# ums.net
KiCad netlist of a schematic drawn in EAGLE
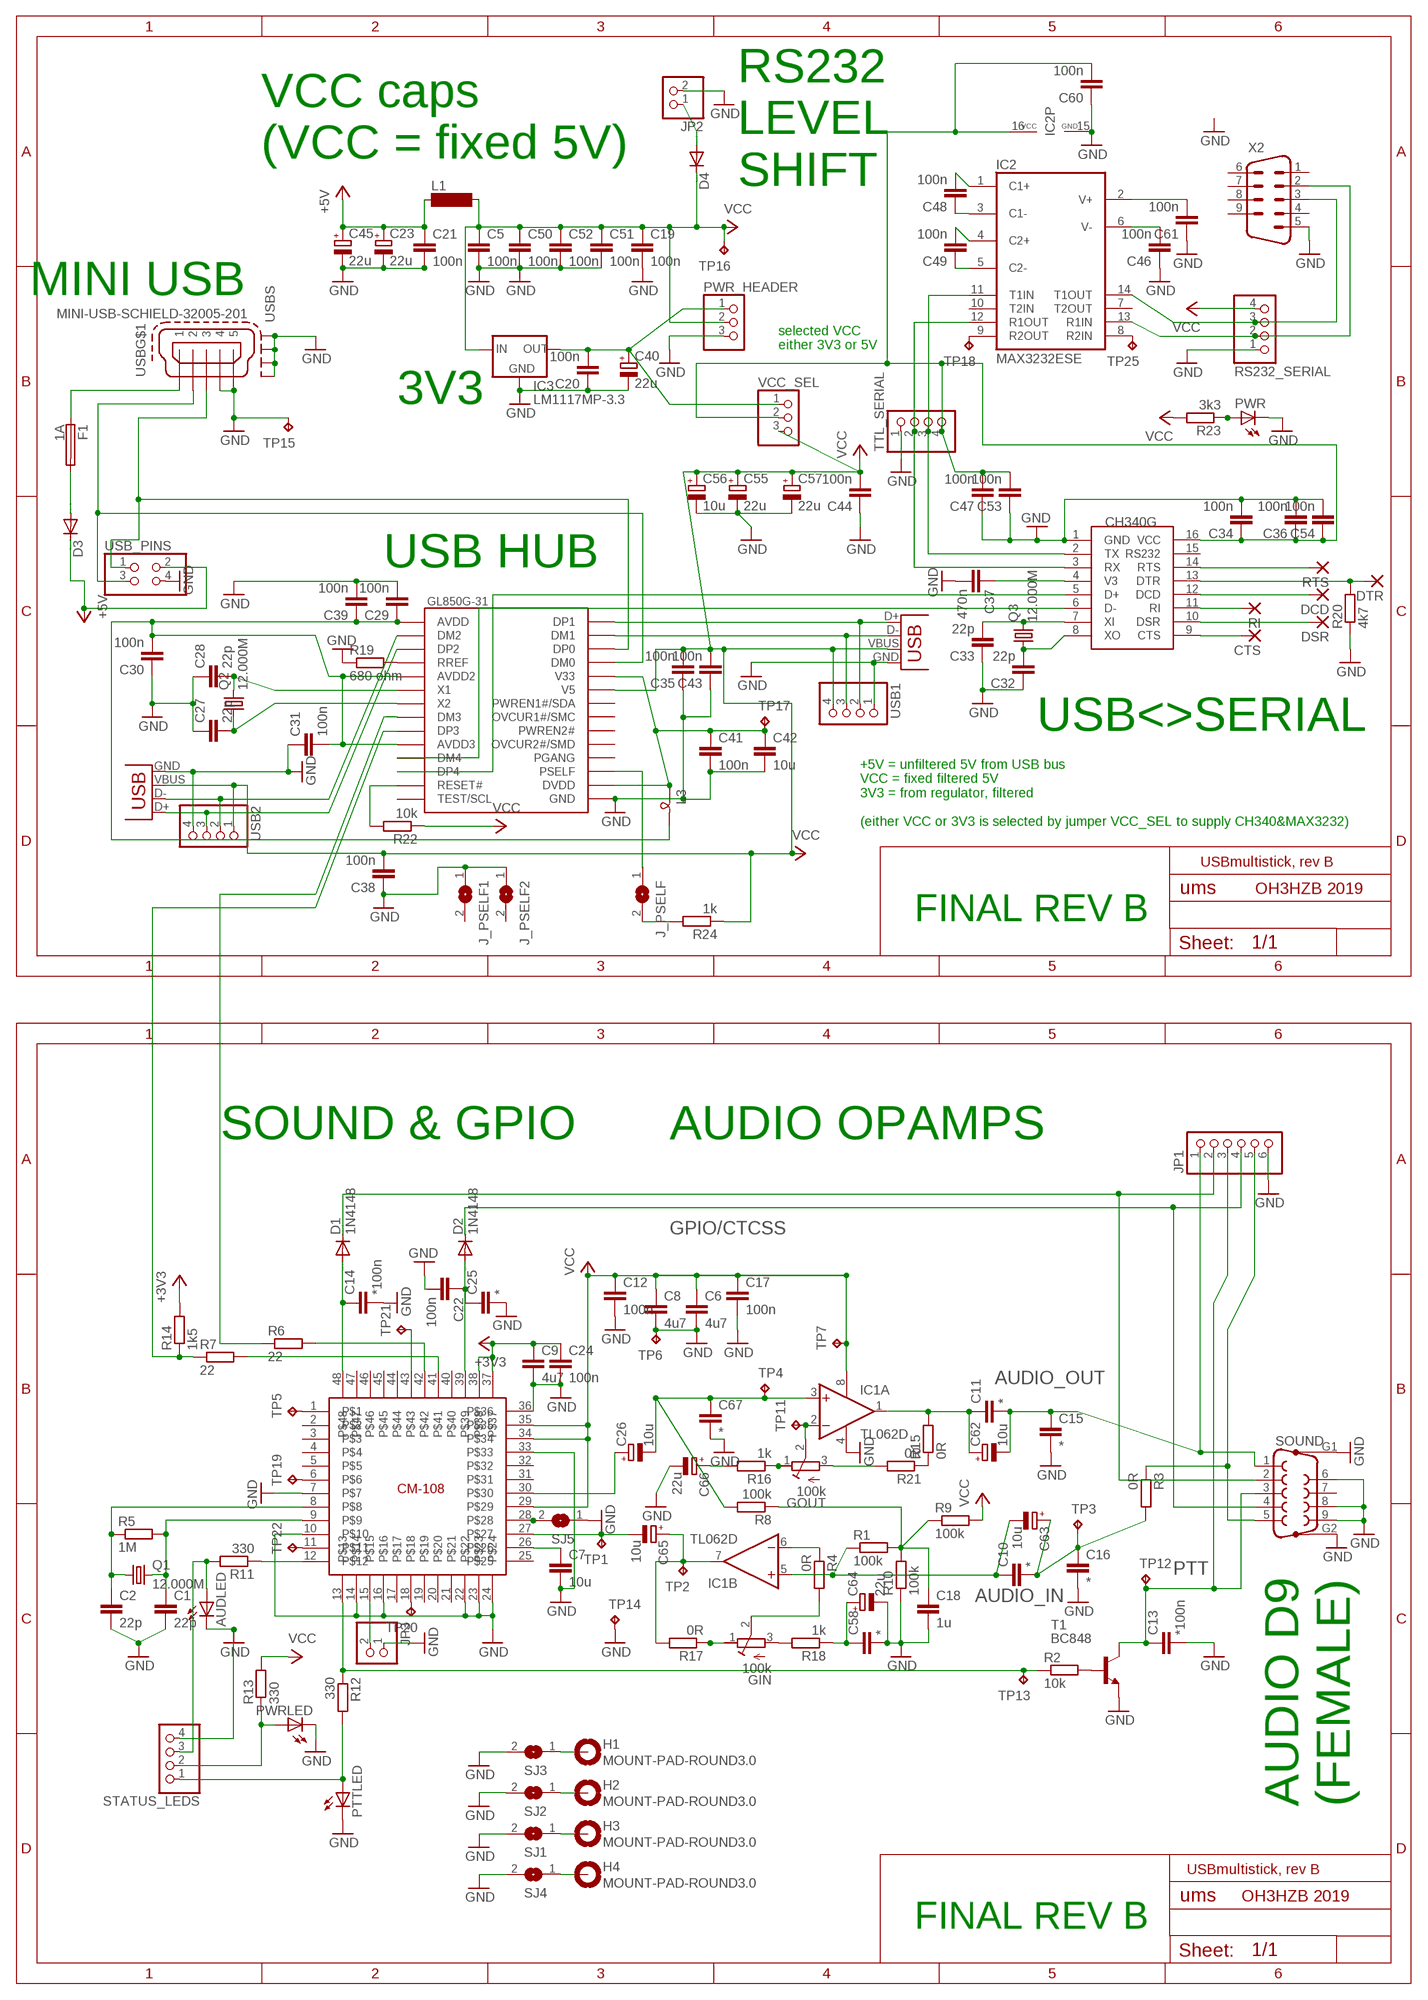
[diagram p0: schematic, sheet 1]

(export (version "E")
  (design (tool "Eeschema 10.0.6"))
  (components
    (comp (ref "AUDLED")
      (value "LED3MM")
      (footprint "eagle-import:LED3MM")
      (libsource (lib "eagle-import") (part "LED3MM"))
    )
    (comp (ref "C1")
      (value "22p")
      (footprint "eagle-import:C1206K")
      (libsource (lib "eagle-import") (part "C-EUC1206K"))
    )
    (comp (ref "C2")
      (value "22p")
      (footprint "eagle-import:C1206K")
      (libsource (lib "eagle-import") (part "C-EUC1206K"))
    )
    (comp (ref "C5")
      (value "100n")
      (footprint "eagle-import:C1206K")
      (libsource (lib "eagle-import") (part "C-EUC1206K"))
    )
    (comp (ref "C6")
      (value "4u7")
      (footprint "eagle-import:C1206K")
      (libsource (lib "eagle-import") (part "C-EUC1206K"))
    )
    (comp (ref "C7")
      (value "10u")
      (footprint "eagle-import:C1206K")
      (libsource (lib "eagle-import") (part "C-EUC1206K"))
    )
    (comp (ref "C8")
      (value "4u7")
      (footprint "eagle-import:C1206K")
      (libsource (lib "eagle-import") (part "C-EUC1206K"))
    )
    (comp (ref "C9")
      (value "4u7")
      (footprint "eagle-import:C1206K")
      (libsource (lib "eagle-import") (part "C-EUC1206K"))
    )
    (comp (ref "C10")
      (value "*")
      (footprint "eagle-import:C1206K")
      (libsource (lib "eagle-import") (part "C-EUC1206K"))
    )
    (comp (ref "C11")
      (value "*")
      (footprint "eagle-import:C1206K")
      (libsource (lib "eagle-import") (part "C-EUC1206K"))
    )
    (comp (ref "C12")
      (value "100n")
      (footprint "eagle-import:C1206K")
      (libsource (lib "eagle-import") (part "C-EUC1206K"))
    )
    (comp (ref "C13")
      (value "*100n")
      (footprint "eagle-import:C1206K")
      (libsource (lib "eagle-import") (part "C-EUC1206K"))
    )
    (comp (ref "C14")
      (value "*100n")
      (footprint "eagle-import:C1206K")
      (libsource (lib "eagle-import") (part "C-EUC1206K"))
    )
    (comp (ref "C15")
      (value "*")
      (footprint "eagle-import:C0805")
      (libsource (lib "eagle-import") (part "C-EUC0805"))
    )
    (comp (ref "C16")
      (value "*")
      (footprint "eagle-import:C1206K")
      (libsource (lib "eagle-import") (part "C-EUC1206K"))
    )
    (comp (ref "C17")
      (value "100n")
      (footprint "eagle-import:C0805")
      (libsource (lib "eagle-import") (part "C-EUC0805"))
    )
    (comp (ref "C18")
      (value "1u")
      (footprint "eagle-import:C4532")
      (libsource (lib "eagle-import") (part "C-EUC4532"))
    )
    (comp (ref "C19")
      (value "100n")
      (footprint "eagle-import:C0805")
      (libsource (lib "eagle-import") (part "C-EUC0805"))
    )
    (comp (ref "C20")
      (value "100n")
      (footprint "eagle-import:C0805")
      (libsource (lib "eagle-import") (part "C-EUC0805"))
    )
    (comp (ref "C21")
      (value "100n")
      (footprint "eagle-import:C0805")
      (libsource (lib "eagle-import") (part "C-EUC0805"))
    )
    (comp (ref "C22")
      (value "100n")
      (footprint "eagle-import:C0805")
      (libsource (lib "eagle-import") (part "C-EUC0805"))
    )
    (comp (ref "C23")
      (value "22u")
      (footprint "eagle-import:D_7343-31W")
      (libsource (lib "eagle-import") (part "CPOL-EUD/7343-31W"))
    )
    (comp (ref "C24")
      (value "100n")
      (footprint "eagle-import:C0805")
      (libsource (lib "eagle-import") (part "C-EUC0805"))
    )
    (comp (ref "C25")
      (value "*")
      (footprint "eagle-import:C0805")
      (libsource (lib "eagle-import") (part "C-EUC0805"))
    )
    (comp (ref "C26")
      (value "10u")
      (footprint "eagle-import:153CLV-0605")
      (libsource (lib "eagle-import") (part "CPOL-EU153CLV-0605"))
    )
    (comp (ref "C27")
      (value "22p")
      (footprint "eagle-import:C1206K")
      (libsource (lib "eagle-import") (part "C-EUC1206K"))
    )
    (comp (ref "C28")
      (value "22p")
      (footprint "eagle-import:C1206K")
      (libsource (lib "eagle-import") (part "C-EUC1206K"))
    )
    (comp (ref "C29")
      (value "100n")
      (footprint "eagle-import:C0805")
      (libsource (lib "eagle-import") (part "C-EUC0805"))
    )
    (comp (ref "C30")
      (value "100n")
      (footprint "eagle-import:C0805")
      (libsource (lib "eagle-import") (part "C-EUC0805"))
    )
    (comp (ref "C31")
      (value "100n")
      (footprint "eagle-import:C1206")
      (libsource (lib "eagle-import") (part "C-EUC1206"))
    )
    (comp (ref "C32")
      (value "22p")
      (footprint "eagle-import:C1206K")
      (libsource (lib "eagle-import") (part "C-EUC1206K"))
    )
    (comp (ref "C33")
      (value "22p")
      (footprint "eagle-import:C1206K")
      (libsource (lib "eagle-import") (part "C-EUC1206K"))
    )
    (comp (ref "C34")
      (value "100n")
      (footprint "eagle-import:C0805")
      (libsource (lib "eagle-import") (part "C-EUC0805"))
    )
    (comp (ref "C35")
      (value "100n")
      (footprint "eagle-import:C0805")
      (libsource (lib "eagle-import") (part "C-EUC0805"))
    )
    (comp (ref "C36")
      (value "100n")
      (footprint "eagle-import:C0805")
      (libsource (lib "eagle-import") (part "C-EUC0805"))
    )
    (comp (ref "C37")
      (value "470n")
      (footprint "eagle-import:C0805")
      (libsource (lib "eagle-import") (part "C-EUC0805"))
    )
    (comp (ref "C38")
      (value "100n")
      (footprint "eagle-import:C0805")
      (libsource (lib "eagle-import") (part "C-EUC0805"))
    )
    (comp (ref "C39")
      (value "100n")
      (footprint "eagle-import:C0805")
      (libsource (lib "eagle-import") (part "C-EUC0805"))
    )
    (comp (ref "C40")
      (value "22u")
      (footprint "eagle-import:SMC_B")
      (libsource (lib "eagle-import") (part "CPOL-EUSMCB"))
    )
    (comp (ref "C41")
      (value "100n")
      (footprint "eagle-import:C0805")
      (libsource (lib "eagle-import") (part "C-EUC0805"))
    )
    (comp (ref "C42")
      (value "10u")
      (footprint "eagle-import:C0805")
      (libsource (lib "eagle-import") (part "C-EUC0805"))
    )
    (comp (ref "C43")
      (value "100n")
      (footprint "eagle-import:C0805")
      (libsource (lib "eagle-import") (part "C-EUC0805"))
    )
    (comp (ref "C44")
      (value "100n")
      (footprint "eagle-import:C0805")
      (libsource (lib "eagle-import") (part "C-EUC0805"))
    )
    (comp (ref "C45")
      (value "22u")
      (footprint "eagle-import:D_7343-31W")
      (libsource (lib "eagle-import") (part "CPOL-EUD/7343-31W"))
    )
    (comp (ref "C46")
      (value "100n")
      (footprint "eagle-import:C0805")
      (libsource (lib "eagle-import") (part "C-EUC0805"))
    )
    (comp (ref "C47")
      (value "100n")
      (footprint "eagle-import:C0805")
      (libsource (lib "eagle-import") (part "C-EUC0805"))
    )
    (comp (ref "C48")
      (value "100n")
      (footprint "eagle-import:C0805")
      (libsource (lib "eagle-import") (part "C-EUC0805"))
    )
    (comp (ref "C49")
      (value "100n")
      (footprint "eagle-import:C0805")
      (libsource (lib "eagle-import") (part "C-EUC0805"))
    )
    (comp (ref "C50")
      (value "100n")
      (footprint "eagle-import:C0805")
      (libsource (lib "eagle-import") (part "C-EUC0805"))
    )
    (comp (ref "C51")
      (value "100n")
      (footprint "eagle-import:C0805")
      (libsource (lib "eagle-import") (part "C-EUC0805"))
    )
    (comp (ref "C52")
      (value "100n")
      (footprint "eagle-import:C0805")
      (libsource (lib "eagle-import") (part "C-EUC0805"))
    )
    (comp (ref "C53")
      (value "100n")
      (footprint "eagle-import:C0805")
      (libsource (lib "eagle-import") (part "C-EUC0805"))
    )
    (comp (ref "C54")
      (value "100n")
      (footprint "eagle-import:C1206")
      (libsource (lib "eagle-import") (part "C-EUC1206"))
    )
    (comp (ref "C55")
      (value "22u")
      (footprint "eagle-import:C_6032-28R")
      (libsource (lib "eagle-import") (part "CPOL-EUC/6032-28R"))
    )
    (comp (ref "C56")
      (value "10u")
      (footprint "eagle-import:SMC_B")
      (libsource (lib "eagle-import") (part "CPOL-EUSMCB"))
    )
    (comp (ref "C57")
      (value "22u")
      (footprint "eagle-import:CT6032")
      (libsource (lib "eagle-import") (part "CPOL-EUCT6032"))
    )
    (comp (ref "C58")
      (value "*")
      (footprint "eagle-import:C1206K")
      (libsource (lib "eagle-import") (part "C-EUC1206K"))
    )
    (comp (ref "C60")
      (value "100n")
      (footprint "eagle-import:C0805")
      (libsource (lib "eagle-import") (part "C-EUC0805"))
    )
    (comp (ref "C61")
      (value "100n")
      (footprint "eagle-import:C0805")
      (libsource (lib "eagle-import") (part "C-EUC0805"))
    )
    (comp (ref "C62")
      (value "10u")
      (footprint "eagle-import:153CLV-0605")
      (libsource (lib "eagle-import") (part "CPOL-EU153CLV-0605"))
    )
    (comp (ref "C63")
      (value "10u")
      (footprint "eagle-import:153CLV-0605")
      (libsource (lib "eagle-import") (part "CPOL-EU153CLV-0605"))
    )
    (comp (ref "C64")
      (value "22u")
      (footprint "eagle-import:153CLV-0605")
      (libsource (lib "eagle-import") (part "CPOL-EU153CLV-0605"))
    )
    (comp (ref "C65")
      (value "10u")
      (footprint "eagle-import:153CLV-0605")
      (libsource (lib "eagle-import") (part "CPOL-EU153CLV-0605"))
    )
    (comp (ref "C66")
      (value "22u")
      (footprint "eagle-import:153CLV-0605")
      (libsource (lib "eagle-import") (part "CPOL-EU153CLV-0605"))
    )
    (comp (ref "C67")
      (value "*")
      (footprint "eagle-import:C0805")
      (libsource (lib "eagle-import") (part "C-EUC0805"))
    )
    (comp (ref "CTS")
      (value "SMD2")
      (footprint "eagle-import:SMD1,27-2,54")
      (libsource (lib "eagle-import") (part "SMD2"))
    )
    (comp (ref "D1")
      (value "1N4148")
      (footprint "eagle-import:SOD123")
      (libsource (lib "eagle-import") (part "DIODE-SOD123"))
    )
    (comp (ref "D2")
      (value "1N4148")
      (footprint "eagle-import:SOD323-W")
      (libsource (lib "eagle-import") (part "DIODE-SOD323-W"))
    )
    (comp (ref "D3")
      (value "DIODE-DO214AC")
      (footprint "eagle-import:DO214AC")
      (libsource (lib "eagle-import") (part "DIODE-DO214AC"))
    )
    (comp (ref "D4")
      (value "DIODE-DO214AC")
      (footprint "eagle-import:DO214AC")
      (libsource (lib "eagle-import") (part "DIODE-DO214AC"))
    )
    (comp (ref "DCD")
      (value "SMD2")
      (footprint "eagle-import:SMD1,27-2,54")
      (libsource (lib "eagle-import") (part "SMD2"))
    )
    (comp (ref "DSR")
      (value "SMD2")
      (footprint "eagle-import:SMD1,27-2,54")
      (libsource (lib "eagle-import") (part "SMD2"))
    )
    (comp (ref "DTR")
      (value "SMD2")
      (footprint "eagle-import:SMD1,27-2,54")
      (libsource (lib "eagle-import") (part "SMD2"))
    )
    (comp (ref "F1")
      (value "1A")
      (footprint "eagle-import:TE5")
      (libsource (lib "eagle-import") (part "TE5"))
    )
    (comp (ref "GIN")
      (value "100k")
      (footprint "eagle-import:RTRIMT93YA")
      (libsource (lib "eagle-import") (part "R-TRIMMT93YA"))
    )
    (comp (ref "GOUT")
      (value "100k")
      (footprint "eagle-import:RTRIMT93YA")
      (libsource (lib "eagle-import") (part "R-TRIMMT93YA"))
    )
    (comp (ref "H1")
      (value "MOUNT-PAD-ROUND3.0")
      (footprint "eagle-import:3,0-PAD")
      (libsource (lib "eagle-import") (part "MOUNT-PAD-ROUND3.0"))
    )
    (comp (ref "H2")
      (value "MOUNT-PAD-ROUND3.0")
      (footprint "eagle-import:3,0-PAD")
      (libsource (lib "eagle-import") (part "MOUNT-PAD-ROUND3.0"))
    )
    (comp (ref "H3")
      (value "MOUNT-PAD-ROUND3.0")
      (footprint "eagle-import:3,0-PAD")
      (libsource (lib "eagle-import") (part "MOUNT-PAD-ROUND3.0"))
    )
    (comp (ref "H4")
      (value "MOUNT-PAD-ROUND3.0")
      (footprint "eagle-import:3,0-PAD")
      (libsource (lib "eagle-import") (part "MOUNT-PAD-ROUND3.0"))
    )
    (comp (ref "IC1")
      (value "TL062D")
      (footprint "eagle-import:SO08")
      (libsource (lib "eagle-import") (part "TL062D"))
    )
    (comp (ref "IC2")
      (value "MAX3232ESE")
      (footprint "eagle-import:SO16")
      (fields (field (name "MF") "MAXIM"))
      (libsource (lib "eagle-import") (part "MAX3232SEE"))
    )
    (comp (ref "IC3")
      (value "LM1117MP-3.3")
      (footprint "eagle-import:SOT223")
      (fields (field (name "MF") "Texas Instruments"))
      (libsource (lib "eagle-import") (part "LM1117?-MP3.3"))
    )
    (comp (ref "IC4")
      (value "GL850G-31")
      (footprint "eagle-import:TSSOP28")
      (libsource (lib "eagle-import") (part "GL850G-31"))
    )
    (comp (ref "JP1")
      (value "PINHD-1X6")
      (footprint "eagle-import:1X06")
      (libsource (lib "eagle-import") (part "PINHD-1X6"))
    )
    (comp (ref "JP2")
      (value "PINHD-1X2")
      (footprint "eagle-import:1X02")
      (libsource (lib "eagle-import") (part "PINHD-1X2"))
    )
    (comp (ref "JP3")
      (value "PINHD-1X2")
      (footprint "eagle-import:1X02")
      (libsource (lib "eagle-import") (part "PINHD-1X2"))
    )
    (comp (ref "J_PSELF")
      (value "SJ")
      (footprint "eagle-import:SJ")
      (libsource (lib "eagle-import") (part "SJ"))
    )
    (comp (ref "J_PSELF1")
      (value "SJ")
      (footprint "eagle-import:SJ")
      (libsource (lib "eagle-import") (part "SJ"))
    )
    (comp (ref "J_PSELF2")
      (value "SJ")
      (footprint "eagle-import:SJ")
      (libsource (lib "eagle-import") (part "SJ"))
    )
    (comp (ref "L1")
      (value "SM-1206")
      (footprint "eagle-import:SM-1206")
      (libsource (lib "eagle-import") (part "SM-1206"))
    )
    (comp (ref "L3")
      (value "SM-B5")
      (footprint "eagle-import:SM-B5")
      (libsource (lib "eagle-import") (part "SM-B5"))
    )
    (comp (ref "PTTLED")
      (value "LED3MM")
      (footprint "eagle-import:LED3MM")
      (libsource (lib "eagle-import") (part "LED3MM"))
    )
    (comp (ref "PWR")
      (value "LEDCHIPLED_0805")
      (footprint "eagle-import:CHIPLED_0805")
      (libsource (lib "eagle-import") (part "LEDCHIPLED_0805"))
    )
    (comp (ref "PWRLED")
      (value "LED3MM")
      (footprint "eagle-import:LED3MM")
      (libsource (lib "eagle-import") (part "LED3MM"))
    )
    (comp (ref "PWR_HEADER")
      (value "PINHD-1X3")
      (footprint "eagle-import:1X03")
      (libsource (lib "eagle-import") (part "PINHD-1X3"))
    )
    (comp (ref "Q1")
      (value "12.000M")
      (footprint "eagle-import:SM49")
      (libsource (lib "eagle-import") (part "CRYSTALSM49"))
    )
    (comp (ref "Q2")
      (value "12.000M")
      (footprint "eagle-import:SM49")
      (libsource (lib "eagle-import") (part "CRYSTALSM49"))
    )
    (comp (ref "Q3")
      (value "12.000M")
      (footprint "eagle-import:SM49")
      (libsource (lib "eagle-import") (part "CRYSTALSM49"))
    )
    (comp (ref "R1")
      (value "100k")
      (footprint "eagle-import:R1206")
      (libsource (lib "eagle-import") (part "resistor_R-EU_R1206"))
    )
    (comp (ref "R2")
      (value "10k")
      (footprint "eagle-import:R1206")
      (libsource (lib "eagle-import") (part "resistor_R-EU_R1206"))
    )
    (comp (ref "R3")
      (value "0R")
      (footprint "eagle-import:R1206")
      (libsource (lib "eagle-import") (part "resistor_R-EU_R1206"))
    )
    (comp (ref "R4")
      (value "0R")
      (footprint "eagle-import:R1206")
      (libsource (lib "eagle-import") (part "resistor_R-EU_R1206"))
    )
    (comp (ref "R5")
      (value "1M")
      (footprint "eagle-import:R1206")
      (libsource (lib "eagle-import") (part "resistor_R-EU_R1206"))
    )
    (comp (ref "R6")
      (value "22")
      (footprint "eagle-import:R1206")
      (libsource (lib "eagle-import") (part "resistor_R-EU_R1206"))
    )
    (comp (ref "R7")
      (value "22")
      (footprint "eagle-import:R1206")
      (libsource (lib "eagle-import") (part "resistor_R-EU_R1206"))
    )
    (comp (ref "R8")
      (value "100k")
      (footprint "eagle-import:R1206")
      (libsource (lib "eagle-import") (part "resistor_R-EU_R1206"))
    )
    (comp (ref "R9")
      (value "100k")
      (footprint "eagle-import:R1206")
      (libsource (lib "eagle-import") (part "resistor_R-EU_R1206"))
    )
    (comp (ref "R10")
      (value "100k")
      (footprint "eagle-import:R1206")
      (libsource (lib "eagle-import") (part "resistor_R-EU_R1206"))
    )
    (comp (ref "R11")
      (value "330")
      (footprint "eagle-import:R1206")
      (libsource (lib "eagle-import") (part "resistor_R-EU_R1206"))
    )
    (comp (ref "R12")
      (value "330")
      (footprint "eagle-import:R1206")
      (libsource (lib "eagle-import") (part "resistor_R-EU_R1206"))
    )
    (comp (ref "R13")
      (value "330")
      (footprint "eagle-import:R1206")
      (libsource (lib "eagle-import") (part "resistor_R-EU_R1206"))
    )
    (comp (ref "R14")
      (value "1k5")
      (footprint "eagle-import:R1206")
      (libsource (lib "eagle-import") (part "resistor_R-EU_R1206"))
    )
    (comp (ref "R15")
      (value "0R")
      (footprint "eagle-import:R1206")
      (libsource (lib "eagle-import") (part "resistor_R-EU_R1206"))
    )
    (comp (ref "R16")
      (value "1k")
      (footprint "eagle-import:R1206")
      (libsource (lib "eagle-import") (part "resistor_R-EU_R1206"))
    )
    (comp (ref "R17")
      (value "0R")
      (footprint "eagle-import:R1206")
      (libsource (lib "eagle-import") (part "resistor_R-EU_R1206"))
    )
    (comp (ref "R18")
      (value "1k")
      (footprint "eagle-import:R1206")
      (libsource (lib "eagle-import") (part "resistor_R-EU_R1206"))
    )
    (comp (ref "R19")
      (value "680 ohm")
      (footprint "eagle-import:R0805")
      (libsource (lib "eagle-import") (part "R-EU_R0805"))
    )
    (comp (ref "R20")
      (value "4k7")
      (footprint "eagle-import:R0805")
      (libsource (lib "eagle-import") (part "resistor_R-EU_R0805"))
    )
    (comp (ref "R21")
      (value "0R")
      (footprint "eagle-import:R1206")
      (libsource (lib "eagle-import") (part "resistor_R-EU_R1206"))
    )
    (comp (ref "R22")
      (value "10k")
      (footprint "eagle-import:R1206")
      (libsource (lib "eagle-import") (part "R-EU_R1206"))
    )
    (comp (ref "R23")
      (value "3k3")
      (footprint "eagle-import:R0805")
      (libsource (lib "eagle-import") (part "resistor_R-EU_R0805"))
    )
    (comp (ref "R24")
      (value "1k")
      (footprint "eagle-import:R0805")
      (libsource (lib "eagle-import") (part "resistor_R-EU_R0805"))
    )
    (comp (ref "RI")
      (value "SMD2")
      (footprint "eagle-import:SMD1,27-2,54")
      (libsource (lib "eagle-import") (part "SMD2"))
    )
    (comp (ref "RS232_SERIAL")
      (value "PINHD-1X4")
      (footprint "eagle-import:1X04")
      (libsource (lib "eagle-import") (part "PINHD-1X4"))
    )
    (comp (ref "RTS")
      (value "SMD2")
      (footprint "eagle-import:SMD1,27-2,54")
      (libsource (lib "eagle-import") (part "SMD2"))
    )
    (comp (ref "SJ1") (value "SJ") (footprint "eagle-import:SJ") (libsource (lib "eagle-import") (part "SJ")))
    (comp (ref "SJ2") (value "SJ") (footprint "eagle-import:SJ") (libsource (lib "eagle-import") (part "SJ")))
    (comp (ref "SJ3") (value "SJ") (footprint "eagle-import:SJ") (libsource (lib "eagle-import") (part "SJ")))
    (comp (ref "SJ4") (value "SJ") (footprint "eagle-import:SJ") (libsource (lib "eagle-import") (part "SJ")))
    (comp (ref "SJ5") (value "SJ") (footprint "eagle-import:SJ") (libsource (lib "eagle-import") (part "SJ")))
    (comp (ref "SOUND")
      (value "F09HP")
      (footprint "eagle-import:F09HP")
      (libsource (lib "eagle-import") (part "F09HP"))
    )
    (comp (ref "STATUS_LEDS")
      (value "PINHD-1X4")
      (footprint "eagle-import:1X04")
      (libsource (lib "eagle-import") (part "PINHD-1X4"))
    )
    (comp (ref "T1")
      (value "BC848")
      (footprint "eagle-import:SOT23-BEC")
      (libsource (lib "eagle-import") (part "-NPN-SOT23-BECBC847"))
    )
    (comp (ref "TP1")
      (value "TPB1,27")
      (footprint "eagle-import:B1,27")
      (libsource (lib "eagle-import") (part "TPB1,27"))
    )
    (comp (ref "TP2")
      (value "TPB1,27")
      (footprint "eagle-import:B1,27")
      (libsource (lib "eagle-import") (part "TPB1,27"))
    )
    (comp (ref "TP3")
      (value "TPB1,27")
      (footprint "eagle-import:B1,27")
      (libsource (lib "eagle-import") (part "TPB1,27"))
    )
    (comp (ref "TP4")
      (value "TPB1,27")
      (footprint "eagle-import:B1,27")
      (libsource (lib "eagle-import") (part "TPB1,27"))
    )
    (comp (ref "TP5")
      (value "TPB1,27")
      (footprint "eagle-import:B1,27")
      (libsource (lib "eagle-import") (part "TPB1,27"))
    )
    (comp (ref "TP6")
      (value "TPB1,27")
      (footprint "eagle-import:B1,27")
      (libsource (lib "eagle-import") (part "TPB1,27"))
    )
    (comp (ref "TP7")
      (value "TPB1,27")
      (footprint "eagle-import:B1,27")
      (libsource (lib "eagle-import") (part "TPB1,27"))
    )
    (comp (ref "TP11")
      (value "TPB1,27")
      (footprint "eagle-import:B1,27")
      (libsource (lib "eagle-import") (part "TPB1,27"))
    )
    (comp (ref "TP12")
      (value "TPB1,27")
      (footprint "eagle-import:B1,27")
      (libsource (lib "eagle-import") (part "TPB1,27"))
    )
    (comp (ref "TP13")
      (value "TPB1,27")
      (footprint "eagle-import:B1,27")
      (libsource (lib "eagle-import") (part "TPB1,27"))
    )
    (comp (ref "TP14")
      (value "TPB1,27")
      (footprint "eagle-import:B1,27")
      (libsource (lib "eagle-import") (part "TPB1,27"))
    )
    (comp (ref "TP15")
      (value "TPB1,27")
      (footprint "eagle-import:B1,27")
      (libsource (lib "eagle-import") (part "TPB1,27"))
    )
    (comp (ref "TP16")
      (value "TPB1,27")
      (footprint "eagle-import:B1,27")
      (libsource (lib "eagle-import") (part "TPB1,27"))
    )
    (comp (ref "TP17")
      (value "TPB1,27")
      (footprint "eagle-import:B1,27")
      (libsource (lib "eagle-import") (part "TPB1,27"))
    )
    (comp (ref "TP18")
      (value "TPB1,27")
      (footprint "eagle-import:B1,27")
      (libsource (lib "eagle-import") (part "TPB1,27"))
    )
    (comp (ref "TP19")
      (value "TPB1,27")
      (footprint "eagle-import:B1,27")
      (libsource (lib "eagle-import") (part "TPB1,27"))
    )
    (comp (ref "TP20")
      (value "TPB1,27")
      (footprint "eagle-import:B1,27")
      (libsource (lib "eagle-import") (part "TPB1,27"))
    )
    (comp (ref "TP21")
      (value "TPB1,27")
      (footprint "eagle-import:B1,27")
      (libsource (lib "eagle-import") (part "TPB1,27"))
    )
    (comp (ref "TP22")
      (value "TPB1,27")
      (footprint "eagle-import:B1,27")
      (libsource (lib "eagle-import") (part "TPB1,27"))
    )
    (comp (ref "TP25")
      (value "TPB1,27")
      (footprint "eagle-import:B1,27")
      (libsource (lib "eagle-import") (part "TPB1,27"))
    )
    (comp (ref "TTL_SERIAL")
      (value "PINHD-1X4")
      (footprint "eagle-import:1X04")
      (libsource (lib "eagle-import") (part "PINHD-1X4"))
    )
    (comp (ref "U$1")
      (value "CM-108")
      (footprint "eagle-import:LQFP-48")
      (libsource (lib "eagle-import") (part "CM-108"))
    )
    (comp (ref "U$6")
      (value "CH340G")
      (footprint "eagle-import:SOIC16")
      (libsource (lib "eagle-import") (part "CH340G"))
    )
    (comp (ref "USB")
      (value "MINI-USB-SCHIELD-32005-201")
      (footprint "eagle-import:32005-201")
      (libsource (lib "eagle-import") (part "MINI-USB-SCHIELD-32005-201"))
    )
    (comp (ref "USB-P1")
      (value "USB-A-H")
      (footprint "eagle-import:USB-A-H")
      (libsource (lib "eagle-import") (part "USB-A-H"))
    )
    (comp (ref "USB-P2")
      (value "USB-A-H")
      (footprint "eagle-import:USB-A-H")
      (libsource (lib "eagle-import") (part "USB-A-H"))
    )
    (comp (ref "USB1")
      (value "PINHD-1X4")
      (footprint "eagle-import:1X04")
      (libsource (lib "eagle-import") (part "PINHD-1X4"))
    )
    (comp (ref "USB2")
      (value "PINHD-1X4")
      (footprint "eagle-import:1X04")
      (libsource (lib "eagle-import") (part "PINHD-1X4"))
    )
    (comp (ref "USB_PINS")
      (value "PINHD-2X2")
      (footprint "eagle-import:2X02")
      (libsource (lib "eagle-import") (part "PINHD-2X2"))
    )
    (comp (ref "VCC_SEL")
      (value "PINHD-1X3")
      (footprint "eagle-import:1X03")
      (libsource (lib "eagle-import") (part "PINHD-1X3"))
    )
    (comp (ref "X2")
      (value "M09HP")
      (footprint "eagle-import:M09HP")
      (libsource (lib "eagle-import") (part "M09HP"))
    )
  )
  (nets
    (net (code "1") (name "+3V3") (class "Default")
      (node (ref "C24") (pin "1") (pinfunction "1_1") (pintype "passive"))
      (node (ref "C9") (pin "1") (pinfunction "1_1") (pintype "passive"))
      (node (ref "R14") (pin "2") (pinfunction "2_2") (pintype "passive"))
      (node (ref "U$1") (pin "37") (pinfunction "P$37_37") (pintype "bidirectional"))
      (node (ref "U$1") (pin "38") (pinfunction "P$38_38") (pintype "bidirectional"))
    )
    (net (code "2") (name "+5V") (class "Default")
      (node (ref "C21") (pin "1") (pinfunction "1_1") (pintype "passive"))
      (node (ref "C23") (pin "+") (pinfunction "+_+") (pintype "passive"))
      (node (ref "C45") (pin "+") (pinfunction "+_+") (pintype "passive"))
      (node (ref "D3") (pin "C") (pinfunction "C_C") (pintype "passive"))
      (node (ref "L1") (pin "1") (pinfunction "1_1") (pintype "passive"))
      (node (ref "USB_PINS") (pin "2") (pinfunction "2_2") (pintype "passive"))
    )
    (net (code "3") (name "/AUDIO_IN") (class "Default")
      (node (ref "C10") (pin "2") (pinfunction "2_2") (pintype "passive"))
      (node (ref "C16") (pin "1") (pinfunction "1_1") (pintype "passive"))
      (node (ref "C63") (pin "+") (pinfunction "+_+") (pintype "passive"))
      (node (ref "R3") (pin "2") (pinfunction "2_2") (pintype "passive"))
      (node (ref "TP3") (pin "TP") (pinfunction "TP_TP") (pintype "input"))
    )
    (net (code "4") (name "/AUDIO_OUT") (class "Default")
      (node (ref "C11") (pin "2") (pinfunction "2_2") (pintype "passive"))
      (node (ref "C15") (pin "1") (pinfunction "1_1") (pintype "passive"))
      (node (ref "C62") (pin "-") (pinfunction "-_-") (pintype "passive"))
      (node (ref "JP1") (pin "1") (pinfunction "1_1") (pintype "passive"))
      (node (ref "SOUND") (pin "1") (pinfunction "1_1") (pintype "passive"))
    )
    (net (code "5") (name "/GPIO{slash}CTCSS") (class "Default")
      (node (ref "D2") (pin "C") (pinfunction "C_C") (pintype "passive"))
      (node (ref "JP1") (pin "4") (pinfunction "4_4") (pintype "passive"))
      (node (ref "SOUND") (pin "4") (pinfunction "4_4") (pintype "passive"))
    )
    (net (code "6") (name "/PTT") (class "Default")
      (node (ref "C13") (pin "1") (pinfunction "1_1") (pintype "passive"))
      (node (ref "JP1") (pin "3") (pinfunction "3_3") (pintype "passive"))
      (node (ref "SOUND") (pin "3") (pinfunction "3_3") (pintype "passive"))
      (node (ref "T1") (pin "C") (pinfunction "C_C") (pintype "passive"))
      (node (ref "TP12") (pin "TP") (pinfunction "TP_TP") (pintype "input"))
    )
    (net (code "7") (name "GND") (class "Default")
      (node (ref "AUDLED") (pin "K") (pinfunction "C_K") (pintype "passive"))
      (node (ref "C1") (pin "2") (pinfunction "2_2") (pintype "passive"))
      (node (ref "C12") (pin "2") (pinfunction "2_2") (pintype "passive"))
      (node (ref "C13") (pin "2") (pinfunction "2_2") (pintype "passive"))
      (node (ref "C14") (pin "2") (pinfunction "2_2") (pintype "passive"))
      (node (ref "C15") (pin "2") (pinfunction "2_2") (pintype "passive"))
      (node (ref "C16") (pin "2") (pinfunction "2_2") (pintype "passive"))
      (node (ref "C17") (pin "2") (pinfunction "2_2") (pintype "passive"))
      (node (ref "C18") (pin "2") (pinfunction "2_2") (pintype "passive"))
      (node (ref "C19") (pin "2") (pinfunction "2_2") (pintype "passive"))
      (node (ref "C2") (pin "2") (pinfunction "2_2") (pintype "passive"))
      (node (ref "C20") (pin "1") (pinfunction "1_1") (pintype "passive"))
      (node (ref "C21") (pin "2") (pinfunction "2_2") (pintype "passive"))
      (node (ref "C22") (pin "2") (pinfunction "2_2") (pintype "passive"))
      (node (ref "C23") (pin "-") (pinfunction "-_-") (pintype "passive"))
      (node (ref "C24") (pin "2") (pinfunction "2_2") (pintype "passive"))
      (node (ref "C25") (pin "2") (pinfunction "2_2") (pintype "passive"))
      (node (ref "C27") (pin "1") (pinfunction "1_1") (pintype "passive"))
      (node (ref "C28") (pin "1") (pinfunction "1_1") (pintype "passive"))
      (node (ref "C29") (pin "2") (pinfunction "2_2") (pintype "passive"))
      (node (ref "C30") (pin "1") (pinfunction "1_1") (pintype "passive"))
      (node (ref "C31") (pin "1") (pinfunction "1_1") (pintype "passive"))
      (node (ref "C32") (pin "1") (pinfunction "1_1") (pintype "passive"))
      (node (ref "C33") (pin "1") (pinfunction "1_1") (pintype "passive"))
      (node (ref "C34") (pin "2") (pinfunction "2_2") (pintype "passive"))
      (node (ref "C35") (pin "1") (pinfunction "1_1") (pintype "passive"))
      (node (ref "C36") (pin "2") (pinfunction "2_2") (pintype "passive"))
      (node (ref "C37") (pin "2") (pinfunction "2_2") (pintype "passive"))
      (node (ref "C38") (pin "1") (pinfunction "1_1") (pintype "passive"))
      (node (ref "C39") (pin "2") (pinfunction "2_2") (pintype "passive"))
      (node (ref "C40") (pin "-") (pinfunction "-_-") (pintype "passive"))
      (node (ref "C41") (pin "2") (pinfunction "2_2") (pintype "passive"))
      (node (ref "C42") (pin "2") (pinfunction "2_2") (pintype "passive"))
      (node (ref "C43") (pin "1") (pinfunction "1_1") (pintype "passive"))
      (node (ref "C44") (pin "1") (pinfunction "1_1") (pintype "passive"))
      (node (ref "C45") (pin "-") (pinfunction "-_-") (pintype "passive"))
      (node (ref "C46") (pin "1") (pinfunction "1_1") (pintype "passive"))
      (node (ref "C47") (pin "1") (pinfunction "1_1") (pintype "passive"))
      (node (ref "C5") (pin "2") (pinfunction "2_2") (pintype "passive"))
      (node (ref "C50") (pin "2") (pinfunction "2_2") (pintype "passive"))
      (node (ref "C51") (pin "2") (pinfunction "2_2") (pintype "passive"))
      (node (ref "C52") (pin "2") (pinfunction "2_2") (pintype "passive"))
      (node (ref "C53") (pin "1") (pinfunction "1_1") (pintype "passive"))
      (node (ref "C54") (pin "2") (pinfunction "2_2") (pintype "passive"))
      (node (ref "C55") (pin "-") (pinfunction "-_-") (pintype "passive"))
      (node (ref "C56") (pin "-") (pinfunction "-_-") (pintype "passive"))
      (node (ref "C57") (pin "-") (pinfunction "-_-") (pintype "passive"))
      (node (ref "C58") (pin "2") (pinfunction "2_2") (pintype "passive"))
      (node (ref "C6") (pin "2") (pinfunction "2_2") (pintype "passive"))
      (node (ref "C60") (pin "1") (pinfunction "1_1") (pintype "passive"))
      (node (ref "C61") (pin "1") (pinfunction "1_1") (pintype "passive"))
      (node (ref "C64") (pin "-") (pinfunction "-_-") (pintype "passive"))
      (node (ref "C66") (pin "-") (pinfunction "-_-") (pintype "passive"))
      (node (ref "C67") (pin "2") (pinfunction "2_2") (pintype "passive"))
      (node (ref "C7") (pin "2") (pinfunction "2_2") (pintype "passive"))
      (node (ref "C8") (pin "2") (pinfunction "2_2") (pintype "passive"))
      (node (ref "C9") (pin "2") (pinfunction "2_2") (pintype "passive"))
      (node (ref "IC1") (pin "4") (pinfunction "V-_4") (pintype "power_in"))
      (node (ref "IC2") (pin "15") (pinfunction "GND_15") (pintype "power_in"))
      (node (ref "IC3") (pin "1") (pinfunction "GND_1") (pintype "input"))
      (node (ref "IC4") (pin "15") (pinfunction "GND_15") (pintype "bidirectional"))
      (node (ref "JP1") (pin "6") (pinfunction "6_6") (pintype "passive"))
      (node (ref "JP2") (pin "2") (pinfunction "2_2") (pintype "passive"))
      (node (ref "JP3") (pin "1") (pinfunction "1_1") (pintype "passive"))
      (node (ref "J_PSELF1") (pin "1") (pinfunction "1_1") (pintype "passive"))
      (node (ref "J_PSELF2") (pin "1") (pinfunction "1_1") (pintype "passive"))
      (node (ref "PTTLED") (pin "K") (pinfunction "C_K") (pintype "passive"))
      (node (ref "PWR") (pin "C") (pinfunction "C_C") (pintype "passive"))
      (node (ref "PWRLED") (pin "K") (pinfunction "C_K") (pintype "passive"))
      (node (ref "PWR_HEADER") (pin "3") (pinfunction "3_3") (pintype "passive"))
      (node (ref "R10") (pin "1") (pinfunction "1_1") (pintype "passive"))
      (node (ref "R19") (pin "1") (pinfunction "1_1") (pintype "passive"))
      (node (ref "R20") (pin "1") (pinfunction "1_1") (pintype "passive"))
      (node (ref "RS232_SERIAL") (pin "1") (pinfunction "1_1") (pintype "passive"))
      (node (ref "SJ1") (pin "2") (pinfunction "2_2") (pintype "passive"))
      (node (ref "SJ2") (pin "2") (pinfunction "2_2") (pintype "passive"))
      (node (ref "SJ3") (pin "2") (pinfunction "2_2") (pintype "passive"))
      (node (ref "SJ4") (pin "2") (pinfunction "2_2") (pintype "passive"))
      (node (ref "SJ5") (pin "1") (pinfunction "1_1") (pintype "passive"))
      (node (ref "SOUND") (pin "6") (pinfunction "6_6") (pintype "passive"))
      (node (ref "SOUND") (pin "8") (pinfunction "8_8") (pintype "passive"))
      (node (ref "SOUND") (pin "9") (pinfunction "9_9") (pintype "passive"))
      (node (ref "SOUND") (pin "G1") (pinfunction "G1_G1") (pintype "passive"))
      (node (ref "SOUND") (pin "G2") (pinfunction "G2_G2") (pintype "passive"))
      (node (ref "STATUS_LEDS") (pin "4") (pinfunction "4_4") (pintype "passive"))
      (node (ref "T1") (pin "E") (pinfunction "E_E") (pintype "passive"))
      (node (ref "TP14") (pin "TP") (pinfunction "TP_TP") (pintype "input"))
      (node (ref "TP15") (pin "TP") (pinfunction "TP_TP") (pintype "input"))
      (node (ref "TP6") (pin "TP") (pinfunction "TP_TP") (pintype "input"))
      (node (ref "TTL_SERIAL") (pin "1") (pinfunction "1_1") (pintype "passive"))
      (node (ref "U$1") (pin "10") (pinfunction "P$10_10") (pintype "bidirectional"))
      (node (ref "U$1") (pin "14") (pinfunction "P$14_14") (pintype "bidirectional"))
      (node (ref "U$1") (pin "16") (pinfunction "P$16_16") (pintype "bidirectional"))
      (node (ref "U$1") (pin "22") (pinfunction "P$22_22") (pintype "bidirectional"))
      (node (ref "U$1") (pin "23") (pinfunction "P$23_23") (pintype "bidirectional"))
      (node (ref "U$1") (pin "24") (pinfunction "P$24_24") (pintype "bidirectional"))
      (node (ref "U$1") (pin "33") (pinfunction "P$33_33") (pintype "bidirectional"))
      (node (ref "U$1") (pin "36") (pinfunction "P$36_36") (pintype "bidirectional"))
      (node (ref "U$1") (pin "7") (pinfunction "P$7_7") (pintype "bidirectional"))
      (node (ref "U$6") (pin "1") (pinfunction "GND_1") (pintype "bidirectional"))
      (node (ref "USB") (pin "4") (pinfunction "4_4") (pintype "passive"))
      (node (ref "USB") (pin "5") (pinfunction "5_5") (pintype "passive"))
      (node (ref "USB") (pin "M1") (pinfunction "S1_M1") (pintype "passive"))
      (node (ref "USB") (pin "M2") (pinfunction "S2_M2") (pintype "passive"))
      (node (ref "USB") (pin "M3") (pinfunction "S3_M3") (pintype "passive"))
      (node (ref "USB") (pin "M4") (pinfunction "S4_M4") (pintype "passive"))
      (node (ref "USB-P1") (pin "GND") (pinfunction "GND_GND") (pintype "bidirectional"))
      (node (ref "USB-P2") (pin "GND") (pinfunction "GND_GND") (pintype "bidirectional"))
      (node (ref "USB1") (pin "1") (pinfunction "1_1") (pintype "passive"))
      (node (ref "USB2") (pin "4") (pinfunction "4_4") (pintype "passive"))
      (node (ref "USB_PINS") (pin "4") (pinfunction "4_4") (pintype "passive"))
      (node (ref "X2") (pin "5") (pinfunction "5_5") (pintype "passive"))
    )
    (net (code "8") (name "Net-(AUDLED-PadA)") (class "Default")
      (node (ref "AUDLED") (pin "A") (pinfunction "A_A") (pintype "passive"))
      (node (ref "R11") (pin "2") (pinfunction "2_2") (pintype "passive"))
      (node (ref "STATUS_LEDS") (pin "3") (pinfunction "3_3") (pintype "passive"))
    )
    (net (code "9") (name "Net-(C18-Pad1)") (class "Default")
      (node (ref "C18") (pin "1") (pinfunction "1_1") (pintype "passive"))
      (node (ref "R1") (pin "2") (pinfunction "2_2") (pintype "passive"))
      (node (ref "R10") (pin "2") (pinfunction "2_2") (pintype "passive"))
      (node (ref "R8") (pin "1") (pinfunction "1_1") (pintype "passive"))
      (node (ref "R9") (pin "1") (pinfunction "1_1") (pintype "passive"))
    )
    (net (code "10") (name "Net-(C20-Pad2)") (class "Default")
      (node (ref "C20") (pin "2") (pinfunction "2_2") (pintype "passive"))
      (node (ref "C40") (pin "+") (pinfunction "+_+") (pintype "passive"))
      (node (ref "IC3") (pin "2") (pinfunction "OUT_2") (pintype "passive"))
      (node (ref "IC3") (pin "4") (pinfunction "OUT_4") (pintype "passive"))
      (node (ref "PWR_HEADER") (pin "1") (pinfunction "1_1") (pintype "passive"))
      (node (ref "VCC_SEL") (pin "1") (pinfunction "1_1") (pintype "passive"))
    )
    (net (code "11") (name "Net-(C58-Pad1)") (class "Default")
      (node (ref "C58") (pin "1") (pinfunction "1_1") (pintype "passive"))
      (node (ref "C64") (pin "+") (pinfunction "+_+") (pintype "passive"))
      (node (ref "R18") (pin "1") (pinfunction "1_1") (pintype "passive"))
    )
    (net (code "12") (name "Net-(C66-Pad+)") (class "Default")
      (node (ref "C66") (pin "+") (pinfunction "+_+") (pintype "passive"))
      (node (ref "R16") (pin "2") (pinfunction "2_2") (pintype "passive"))
    )
    (net (code "13") (name "Net-(CTS-P)") (class "Default")
      (node (ref "CTS") (pin "1") (pinfunction "P_1") (pintype "passive"))
      (node (ref "U$6") (pin "9") (pinfunction "CTS_9") (pintype "bidirectional"))
    )
    (net (code "14") (name "Net-(D1-PadC)") (class "Default")
      (node (ref "D1") (pin "C") (pinfunction "C_C") (pintype "passive"))
      (node (ref "JP1") (pin "2") (pinfunction "2_2") (pintype "passive"))
      (node (ref "SOUND") (pin "2") (pinfunction "2_2") (pintype "passive"))
    )
    (net (code "15") (name "Net-(D3-PadA)") (class "Default")
      (node (ref "D3") (pin "A") (pinfunction "A_A") (pintype "passive"))
      (node (ref "F1") (pin "2") (pinfunction "2_2") (pintype "passive"))
    )
    (net (code "16") (name "Net-(D4-PadA)") (class "Default")
      (node (ref "D4") (pin "A") (pinfunction "A_A") (pintype "passive"))
      (node (ref "JP2") (pin "1") (pinfunction "1_1") (pintype "passive"))
    )
    (net (code "17") (name "Net-(DCD-P)") (class "Default")
      (node (ref "DCD") (pin "1") (pinfunction "P_1") (pintype "passive"))
      (node (ref "U$6") (pin "12") (pinfunction "DCD_12") (pintype "bidirectional"))
    )
    (net (code "18") (name "Net-(DSR-P)") (class "Default")
      (node (ref "DSR") (pin "1") (pinfunction "P_1") (pintype "passive"))
      (node (ref "U$6") (pin "10") (pinfunction "DSR_10") (pintype "bidirectional"))
    )
    (net (code "19") (name "Net-(DTR-P)") (class "Default")
      (node (ref "DTR") (pin "1") (pinfunction "P_1") (pintype "passive"))
      (node (ref "R20") (pin "2") (pinfunction "2_2") (pintype "passive"))
      (node (ref "U$6") (pin "13") (pinfunction "DTR_13") (pintype "bidirectional"))
    )
    (net (code "20") (name "Net-(F1-Pad1)") (class "Default")
      (node (ref "F1") (pin "1") (pinfunction "1_1") (pintype "passive"))
      (node (ref "USB") (pin "1") (pinfunction "1_1") (pintype "passive"))
    )
    (net (code "21") (name "Net-(GIN-A)") (class "Default")
      (node (ref "GIN") (pin "1") (pinfunction "A_1") (pintype "passive"))
      (node (ref "R17") (pin "1") (pinfunction "1_1") (pintype "passive"))
    )
    (net (code "22") (name "Net-(GIN-E)") (class "Default")
      (node (ref "GIN") (pin "3") (pinfunction "E_3") (pintype "passive"))
      (node (ref "R18") (pin "2") (pinfunction "2_2") (pintype "passive"))
    )
    (net (code "23") (name "Net-(GIN-S)") (class "Default")
      (node (ref "GIN") (pin "2") (pinfunction "S_2") (pintype "passive"))
      (node (ref "R4") (pin "2") (pinfunction "2_2") (pintype "passive"))
    )
    (net (code "24") (name "Net-(GOUT-A)") (class "Default")
      (node (ref "GOUT") (pin "1") (pinfunction "A_1") (pintype "passive"))
      (node (ref "R16") (pin "1") (pinfunction "1_1") (pintype "passive"))
    )
    (net (code "25") (name "Net-(GOUT-E)") (class "Default")
      (node (ref "GOUT") (pin "3") (pinfunction "E_3") (pintype "passive"))
      (node (ref "R21") (pin "2") (pinfunction "2_2") (pintype "passive"))
    )
    (net (code "26") (name "Net-(GOUT-S)") (class "Default")
      (node (ref "GOUT") (pin "2") (pinfunction "S_2") (pintype "passive"))
      (node (ref "IC1") (pin "2") (pinfunction "-IN_2") (pintype "input"))
      (node (ref "TP11") (pin "TP") (pinfunction "TP_TP") (pintype "input"))
    )
    (net (code "27") (name "Net-(H1-MOUNT)") (class "Default")
      (node (ref "H1") (pin "B3,0") (pinfunction "MOUNT_B3,0") (pintype "passive"))
      (node (ref "SJ3") (pin "1") (pinfunction "1_1") (pintype "passive"))
    )
    (net (code "28") (name "Net-(H2-MOUNT)") (class "Default")
      (node (ref "H2") (pin "B3,0") (pinfunction "MOUNT_B3,0") (pintype "passive"))
      (node (ref "SJ2") (pin "1") (pinfunction "1_1") (pintype "passive"))
    )
    (net (code "29") (name "Net-(H3-MOUNT)") (class "Default")
      (node (ref "H3") (pin "B3,0") (pinfunction "MOUNT_B3,0") (pintype "passive"))
      (node (ref "SJ1") (pin "1") (pinfunction "1_1") (pintype "passive"))
    )
    (net (code "30") (name "Net-(H4-MOUNT)") (class "Default")
      (node (ref "H4") (pin "B3,0") (pinfunction "MOUNT_B3,0") (pintype "passive"))
      (node (ref "SJ4") (pin "1") (pinfunction "1_1") (pintype "passive"))
    )
    (net (code "31") (name "Net-(IC1A-+IN)") (class "Default")
      (node (ref "C26") (pin "-") (pinfunction "-_-") (pintype "passive"))
      (node (ref "C67") (pin "1") (pinfunction "1_1") (pintype "passive"))
      (node (ref "IC1") (pin "3") (pinfunction "+IN_3") (pintype "input"))
      (node (ref "R8") (pin "2") (pinfunction "2_2") (pintype "passive"))
      (node (ref "TP4") (pin "TP") (pinfunction "TP_TP") (pintype "input"))
    )
    (net (code "32") (name "Net-(IC1A-OUT)") (class "Default")
      (node (ref "C11") (pin "1") (pinfunction "1_1") (pintype "passive"))
      (node (ref "C62") (pin "+") (pinfunction "+_+") (pintype "passive"))
      (node (ref "IC1") (pin "1") (pinfunction "OUT_1") (pintype "output"))
      (node (ref "R15") (pin "2") (pinfunction "2_2") (pintype "passive"))
    )
    (net (code "33") (name "Net-(IC1B-+IN)") (class "Default")
      (node (ref "C10") (pin "1") (pinfunction "1_1") (pintype "passive"))
      (node (ref "C63") (pin "-") (pinfunction "-_-") (pintype "passive"))
      (node (ref "IC1") (pin "5") (pinfunction "+IN_5") (pintype "input"))
      (node (ref "R1") (pin "1") (pinfunction "1_1") (pintype "passive"))
    )
    (net (code "34") (name "Net-(IC1B--IN)") (class "Default")
      (node (ref "IC1") (pin "6") (pinfunction "-IN_6") (pintype "input"))
      (node (ref "R4") (pin "1") (pinfunction "1_1") (pintype "passive"))
    )
    (net (code "35") (name "Net-(IC1B-OUT)") (class "Default")
      (node (ref "C65") (pin "+") (pinfunction "+_+") (pintype "passive"))
      (node (ref "IC1") (pin "7") (pinfunction "OUT_7") (pintype "output"))
      (node (ref "R17") (pin "2") (pinfunction "2_2") (pintype "passive"))
      (node (ref "TP2") (pin "TP") (pinfunction "TP_TP") (pintype "input"))
    )
    (net (code "36") (name "Net-(IC2A-C1+)") (class "Default")
      (node (ref "C48") (pin "2") (pinfunction "2_2") (pintype "passive"))
      (node (ref "IC2") (pin "1") (pinfunction "C1+_1") (pintype "bidirectional"))
    )
    (net (code "37") (name "Net-(IC2A-C1-)") (class "Default")
      (node (ref "C48") (pin "1") (pinfunction "1_1") (pintype "passive"))
      (node (ref "IC2") (pin "3") (pinfunction "C1-_3") (pintype "bidirectional"))
    )
    (net (code "38") (name "Net-(IC2A-C2+)") (class "Default")
      (node (ref "C49") (pin "2") (pinfunction "2_2") (pintype "passive"))
      (node (ref "IC2") (pin "4") (pinfunction "C2+_4") (pintype "bidirectional"))
    )
    (net (code "39") (name "Net-(IC2A-C2-)") (class "Default")
      (node (ref "C49") (pin "1") (pinfunction "1_1") (pintype "passive"))
      (node (ref "IC2") (pin "5") (pinfunction "C2-_5") (pintype "bidirectional"))
    )
    (net (code "40") (name "Net-(IC2A-R1IN)") (class "Default")
      (node (ref "IC2") (pin "13") (pinfunction "R1IN_13") (pintype "input"))
      (node (ref "RS232_SERIAL") (pin "2") (pinfunction "2_2") (pintype "passive"))
      (node (ref "X2") (pin "2") (pinfunction "2_2") (pintype "passive"))
    )
    (net (code "41") (name "Net-(IC2A-R1OUT)") (class "Default")
      (node (ref "IC2") (pin "12") (pinfunction "R1OUT_12") (pintype "output"))
      (node (ref "TTL_SERIAL") (pin "2") (pinfunction "2_2") (pintype "passive"))
      (node (ref "U$6") (pin "3") (pinfunction "RX_3") (pintype "bidirectional"))
    )
    (net (code "42") (name "Net-(IC2A-R2IN)") (class "Default")
      (node (ref "IC2") (pin "8") (pinfunction "R2IN_8") (pintype "input"))
      (node (ref "TP25") (pin "TP") (pinfunction "TP_TP") (pintype "input"))
    )
    (net (code "43") (name "Net-(IC2A-R2OUT)") (class "Default")
      (node (ref "IC2") (pin "9") (pinfunction "R2OUT_9") (pintype "output"))
      (node (ref "TP18") (pin "TP") (pinfunction "TP_TP") (pintype "input"))
    )
    (net (code "44") (name "Net-(IC2A-T1IN)") (class "Default")
      (node (ref "IC2") (pin "11") (pinfunction "T1IN_11") (pintype "input"))
      (node (ref "TTL_SERIAL") (pin "3") (pinfunction "3_3") (pintype "passive"))
      (node (ref "U$6") (pin "2") (pinfunction "TX_2") (pintype "bidirectional"))
    )
    (net (code "45") (name "Net-(IC2A-T1OUT)") (class "Default")
      (node (ref "IC2") (pin "14") (pinfunction "T1OUT_14") (pintype "output"))
      (node (ref "RS232_SERIAL") (pin "3") (pinfunction "3_3") (pintype "passive"))
      (node (ref "X2") (pin "3") (pinfunction "3_3") (pintype "passive"))
    )
    (net (code "46") (name "Net-(IC2A-V+)") (class "Default")
      (node (ref "C61") (pin "2") (pinfunction "2_2") (pintype "passive"))
      (node (ref "IC2") (pin "2") (pinfunction "V+_2") (pintype "bidirectional"))
    )
    (net (code "47") (name "Net-(IC2A-V-)") (class "Default")
      (node (ref "C46") (pin "2") (pinfunction "2_2") (pintype "passive"))
      (node (ref "IC2") (pin "6") (pinfunction "V-_6") (pintype "bidirectional"))
    )
    (net (code "48") (name "Net-(IC2B-VCC)") (class "Default")
      (node (ref "C34") (pin "1") (pinfunction "1_1") (pintype "passive"))
      (node (ref "C36") (pin "1") (pinfunction "1_1") (pintype "passive"))
      (node (ref "C47") (pin "2") (pinfunction "2_2") (pintype "passive"))
      (node (ref "C53") (pin "2") (pinfunction "2_2") (pintype "passive"))
      (node (ref "C54") (pin "1") (pinfunction "1_1") (pintype "passive"))
      (node (ref "C60") (pin "2") (pinfunction "2_2") (pintype "passive"))
      (node (ref "IC2") (pin "16") (pinfunction "VCC_16") (pintype "power_in"))
      (node (ref "TTL_SERIAL") (pin "4") (pinfunction "4_4") (pintype "passive"))
      (node (ref "U$6") (pin "16") (pinfunction "VCC_16") (pintype "bidirectional"))
      (node (ref "VCC_SEL") (pin "2") (pinfunction "2_2") (pintype "passive"))
    )
    (net (code "49") (name "Net-(IC4-AVDD)") (class "Default")
      (node (ref "C29") (pin "1") (pinfunction "1_1") (pintype "passive"))
      (node (ref "C30") (pin "2") (pinfunction "2_2") (pintype "passive"))
      (node (ref "C31") (pin "2") (pinfunction "2_2") (pintype "passive"))
      (node (ref "C39") (pin "1") (pinfunction "1_1") (pintype "passive"))
      (node (ref "IC4") (pin "1") (pinfunction "AVDD_1") (pintype "bidirectional"))
      (node (ref "IC4") (pin "10") (pinfunction "AVDD3_10") (pintype "bidirectional"))
      (node (ref "IC4") (pin "5") (pinfunction "AVDD2_5") (pintype "bidirectional"))
      (node (ref "L3") (pin "2") (pinfunction "2_2") (pintype "passive"))
    )
    (net (code "50") (name "Net-(IC4-DM0)") (class "Default")
      (node (ref "IC4") (pin "25") (pinfunction "DM0_25") (pintype "bidirectional"))
      (node (ref "USB") (pin "2") (pinfunction "2_2") (pintype "passive"))
      (node (ref "USB_PINS") (pin "3") (pinfunction "3_3") (pintype "passive"))
    )
    (net (code "51") (name "Net-(IC4-DM1)") (class "Default")
      (node (ref "IC4") (pin "27") (pinfunction "DM1_27") (pintype "bidirectional"))
      (node (ref "USB-P2") (pin "D-") (pinfunction "D-_D-") (pintype "bidirectional"))
      (node (ref "USB1") (pin "3") (pinfunction "3_3") (pintype "passive"))
    )
    (net (code "52") (name "Net-(IC4-DM2)") (class "Default")
      (node (ref "IC4") (pin "2") (pinfunction "DM2_2") (pintype "bidirectional"))
      (node (ref "USB-P1") (pin "D-") (pinfunction "D-_D-") (pintype "bidirectional"))
      (node (ref "USB2") (pin "2") (pinfunction "2_2") (pintype "passive"))
    )
    (net (code "53") (name "Net-(IC4-DM3)") (class "Default")
      (node (ref "IC4") (pin "8") (pinfunction "DM3_8") (pintype "bidirectional"))
      (node (ref "R6") (pin "1") (pinfunction "1_1") (pintype "passive"))
    )
    (net (code "54") (name "Net-(IC4-DM4)") (class "Default")
      (node (ref "IC4") (pin "11") (pinfunction "DM4_11") (pintype "bidirectional"))
      (node (ref "U$6") (pin "6") (pinfunction "D-_6") (pintype "bidirectional"))
    )
    (net (code "55") (name "Net-(IC4-DP0)") (class "Default")
      (node (ref "IC4") (pin "26") (pinfunction "DP0_26") (pintype "bidirectional"))
      (node (ref "USB") (pin "3") (pinfunction "3_3") (pintype "passive"))
      (node (ref "USB_PINS") (pin "1") (pinfunction "1_1") (pintype "passive"))
    )
    (net (code "56") (name "Net-(IC4-DP1)") (class "Default")
      (node (ref "IC4") (pin "28") (pinfunction "DP1_28") (pintype "bidirectional"))
      (node (ref "USB-P2") (pin "D+") (pinfunction "D+_D+") (pintype "bidirectional"))
      (node (ref "USB1") (pin "2") (pinfunction "2_2") (pintype "passive"))
    )
    (net (code "57") (name "Net-(IC4-DP2)") (class "Default")
      (node (ref "IC4") (pin "3") (pinfunction "DP2_3") (pintype "bidirectional"))
      (node (ref "USB-P1") (pin "D+") (pinfunction "D+_D+") (pintype "bidirectional"))
      (node (ref "USB2") (pin "3") (pinfunction "3_3") (pintype "passive"))
    )
    (net (code "58") (name "Net-(IC4-DP3)") (class "Default")
      (node (ref "IC4") (pin "9") (pinfunction "DP3_9") (pintype "bidirectional"))
      (node (ref "R14") (pin "1") (pinfunction "1_1") (pintype "passive"))
      (node (ref "R7") (pin "1") (pinfunction "1_1") (pintype "passive"))
    )
    (net (code "59") (name "Net-(IC4-DP4)") (class "Default")
      (node (ref "IC4") (pin "12") (pinfunction "DP4_12") (pintype "bidirectional"))
      (node (ref "U$6") (pin "5") (pinfunction "D+_5") (pintype "bidirectional"))
    )
    (net (code "60") (name "Net-(IC4-DVDD)") (class "Default")
      (node (ref "C41") (pin "1") (pinfunction "1_1") (pintype "passive"))
      (node (ref "C42") (pin "1") (pinfunction "1_1") (pintype "passive"))
      (node (ref "IC4") (pin "16") (pinfunction "DVDD_16") (pintype "bidirectional"))
      (node (ref "IC4") (pin "24") (pinfunction "V33_24") (pintype "bidirectional"))
      (node (ref "L3") (pin "1") (pinfunction "1_1") (pintype "passive"))
      (node (ref "TP17") (pin "TP") (pinfunction "TP_TP") (pintype "input"))
    )
    (net (code "61") (name "Net-(IC4-PSELF)") (class "Default")
      (node (ref "IC4") (pin "17") (pinfunction "PSELF_17") (pintype "bidirectional"))
      (node (ref "J_PSELF") (pin "1") (pinfunction "1_1") (pintype "passive"))
    )
    (net (code "62") (name "Net-(IC4-RESET#)") (class "Default")
      (node (ref "IC4") (pin "13") (pinfunction "RESET#_13") (pintype "bidirectional"))
      (node (ref "R22") (pin "2") (pinfunction "2_2") (pintype "passive"))
    )
    (net (code "63") (name "Net-(IC4-RREF)") (class "Default")
      (node (ref "IC4") (pin "4") (pinfunction "RREF_4") (pintype "bidirectional"))
      (node (ref "R19") (pin "2") (pinfunction "2_2") (pintype "passive"))
    )
    (net (code "64") (name "Net-(IC4-X1)") (class "Default")
      (node (ref "C28") (pin "2") (pinfunction "2_2") (pintype "passive"))
      (node (ref "IC4") (pin "6") (pinfunction "X1_6") (pintype "bidirectional"))
      (node (ref "Q2") (pin "2") (pinfunction "2_2") (pintype "passive"))
    )
    (net (code "65") (name "Net-(IC4-X2)") (class "Default")
      (node (ref "C27") (pin "2") (pinfunction "2_2") (pintype "passive"))
      (node (ref "IC4") (pin "7") (pinfunction "X2_7") (pintype "bidirectional"))
      (node (ref "Q2") (pin "1") (pinfunction "1_1") (pintype "passive"))
    )
    (net (code "66") (name "Net-(JP1-Pad5)") (class "Default")
      (node (ref "JP1") (pin "5") (pinfunction "5_5") (pintype "passive"))
      (node (ref "R3") (pin "1") (pinfunction "1_1") (pintype "passive"))
      (node (ref "SOUND") (pin "5") (pinfunction "5_5") (pintype "passive"))
    )
    (net (code "67") (name "Net-(J_PSELF-Pad2)") (class "Default")
      (node (ref "J_PSELF") (pin "2") (pinfunction "2_2") (pintype "passive"))
      (node (ref "R24") (pin "2") (pinfunction "2_2") (pintype "passive"))
    )
    (net (code "68") (name "Net-(PTTLED-PadA)") (class "Default")
      (node (ref "PTTLED") (pin "A") (pinfunction "A_A") (pintype "passive"))
      (node (ref "R12") (pin "2") (pinfunction "2_2") (pintype "passive"))
      (node (ref "STATUS_LEDS") (pin "1") (pinfunction "1_1") (pintype "passive"))
    )
    (net (code "69") (name "Net-(PWR-PadA)") (class "Default")
      (node (ref "PWR") (pin "A") (pinfunction "A_A") (pintype "passive"))
      (node (ref "R23") (pin "1") (pinfunction "1_1") (pintype "passive"))
    )
    (net (code "70") (name "Net-(PWRLED-PadA)") (class "Default")
      (node (ref "PWRLED") (pin "A") (pinfunction "A_A") (pintype "passive"))
      (node (ref "R13") (pin "1") (pinfunction "1_1") (pintype "passive"))
      (node (ref "STATUS_LEDS") (pin "2") (pinfunction "2_2") (pintype "passive"))
    )
    (net (code "71") (name "Net-(R2-Pad2)") (class "Default")
      (node (ref "R2") (pin "2") (pinfunction "2_2") (pintype "passive"))
      (node (ref "T1") (pin "B") (pinfunction "B_B") (pintype "passive"))
    )
    (net (code "72") (name "Net-(R15-Pad1)") (class "Default")
      (node (ref "R15") (pin "1") (pinfunction "1_1") (pintype "passive"))
      (node (ref "R21") (pin "1") (pinfunction "1_1") (pintype "passive"))
    )
    (net (code "73") (name "Net-(RI-P)") (class "Default")
      (node (ref "RI") (pin "1") (pinfunction "P_1") (pintype "passive"))
      (node (ref "U$6") (pin "11") (pinfunction "RI_11") (pintype "bidirectional"))
    )
    (net (code "74") (name "Net-(RTS-P)") (class "Default")
      (node (ref "RTS") (pin "1") (pinfunction "P_1") (pintype "passive"))
      (node (ref "U$6") (pin "14") (pinfunction "RTS_14") (pintype "bidirectional"))
    )
    (net (code "75") (name "Net-(U$1-P$1)") (class "Default")
      (node (ref "TP5") (pin "TP") (pinfunction "TP_TP") (pintype "input"))
      (node (ref "U$1") (pin "1") (pinfunction "P$1_1") (pintype "bidirectional"))
    )
    (net (code "76") (name "Net-(U$1-P$6)") (class "Default")
      (node (ref "TP19") (pin "TP") (pinfunction "TP_TP") (pintype "input"))
      (node (ref "U$1") (pin "6") (pinfunction "P$6_6") (pintype "bidirectional"))
    )
    (net (code "77") (name "Net-(U$1-P$8)") (class "Default")
      (node (ref "C2") (pin "1") (pinfunction "1_1") (pintype "passive"))
      (node (ref "Q1") (pin "1") (pinfunction "1_1") (pintype "passive"))
      (node (ref "R5") (pin "1") (pinfunction "1_1") (pintype "passive"))
      (node (ref "U$1") (pin "8") (pinfunction "P$8_8") (pintype "bidirectional"))
    )
    (net (code "78") (name "Net-(U$1-P$9)") (class "Default")
      (node (ref "C1") (pin "1") (pinfunction "1_1") (pintype "passive"))
      (node (ref "Q1") (pin "2") (pinfunction "2_2") (pintype "passive"))
      (node (ref "R5") (pin "2") (pinfunction "2_2") (pintype "passive"))
      (node (ref "U$1") (pin "9") (pinfunction "P$9_9") (pintype "bidirectional"))
    )
    (net (code "79") (name "Net-(U$1-P$11)") (class "Default")
      (node (ref "TP22") (pin "TP") (pinfunction "TP_TP") (pintype "input"))
      (node (ref "U$1") (pin "11") (pinfunction "P$11_11") (pintype "bidirectional"))
    )
    (net (code "80") (name "Net-(U$1-P$12)") (class "Default")
      (node (ref "R11") (pin "1") (pinfunction "1_1") (pintype "passive"))
      (node (ref "U$1") (pin "12") (pinfunction "P$12_12") (pintype "bidirectional"))
    )
    (net (code "81") (name "Net-(U$1-P$13)") (class "Default")
      (node (ref "R12") (pin "1") (pinfunction "1_1") (pintype "passive"))
      (node (ref "R2") (pin "1") (pinfunction "1_1") (pintype "passive"))
      (node (ref "TP13") (pin "TP") (pinfunction "TP_TP") (pintype "input"))
      (node (ref "U$1") (pin "13") (pinfunction "P$13_13") (pintype "bidirectional"))
    )
    (net (code "82") (name "Net-(U$1-P$15)") (class "Default")
      (node (ref "JP3") (pin "2") (pinfunction "2_2") (pintype "passive"))
      (node (ref "U$1") (pin "15") (pinfunction "P$15_15") (pintype "bidirectional"))
    )
    (net (code "83") (name "Net-(U$1-P$18)") (class "Default")
      (node (ref "TP20") (pin "TP") (pinfunction "TP_TP") (pintype "input"))
      (node (ref "U$1") (pin "18") (pinfunction "P$18_18") (pintype "bidirectional"))
    )
    (net (code "84") (name "Net-(U$1-P$26)") (class "Default")
      (node (ref "C7") (pin "1") (pinfunction "1_1") (pintype "passive"))
      (node (ref "U$1") (pin "26") (pinfunction "P$26_26") (pintype "bidirectional"))
    )
    (net (code "85") (name "Net-(U$1-P$27)") (class "Default")
      (node (ref "C65") (pin "-") (pinfunction "-_-") (pintype "passive"))
      (node (ref "TP1") (pin "TP") (pinfunction "TP_TP") (pintype "input"))
      (node (ref "U$1") (pin "27") (pinfunction "P$27_27") (pintype "bidirectional"))
    )
    (net (code "86") (name "Net-(U$1-P$28)") (class "Default")
      (node (ref "SJ5") (pin "2") (pinfunction "2_2") (pintype "passive"))
      (node (ref "U$1") (pin "28") (pinfunction "P$28_28") (pintype "bidirectional"))
    )
    (net (code "87") (name "Net-(U$1-P$30)") (class "Default")
      (node (ref "C26") (pin "+") (pinfunction "+_+") (pintype "passive"))
      (node (ref "U$1") (pin "30") (pinfunction "P$30_30") (pintype "bidirectional"))
    )
    (net (code "88") (name "Net-(U$1-P$39)") (class "Default")
      (node (ref "C22") (pin "1") (pinfunction "1_1") (pintype "passive"))
      (node (ref "C25") (pin "1") (pinfunction "1_1") (pintype "passive"))
      (node (ref "D2") (pin "A") (pinfunction "A_A") (pintype "passive"))
      (node (ref "U$1") (pin "39") (pinfunction "P$39_39") (pintype "bidirectional"))
    )
    (net (code "89") (name "Net-(U$1-P$41)") (class "Default")
      (node (ref "R7") (pin "2") (pinfunction "2_2") (pintype "passive"))
      (node (ref "U$1") (pin "41") (pinfunction "P$41_41") (pintype "bidirectional"))
    )
    (net (code "90") (name "Net-(U$1-P$42)") (class "Default")
      (node (ref "R6") (pin "2") (pinfunction "2_2") (pintype "passive"))
      (node (ref "U$1") (pin "42") (pinfunction "P$42_42") (pintype "bidirectional"))
    )
    (net (code "91") (name "Net-(U$1-P$43)") (class "Default")
      (node (ref "TP21") (pin "TP") (pinfunction "TP_TP") (pintype "input"))
      (node (ref "U$1") (pin "43") (pinfunction "P$43_43") (pintype "bidirectional"))
    )
    (net (code "92") (name "Net-(U$1-P$48)") (class "Default")
      (node (ref "C14") (pin "1") (pinfunction "1_1") (pintype "passive"))
      (node (ref "D1") (pin "A") (pinfunction "A_A") (pintype "passive"))
      (node (ref "U$1") (pin "48") (pinfunction "P$48_48") (pintype "bidirectional"))
    )
    (net (code "93") (name "Net-(U$6-V3)") (class "Default")
      (node (ref "C37") (pin "1") (pinfunction "1_1") (pintype "passive"))
      (node (ref "U$6") (pin "4") (pinfunction "V3_4") (pintype "bidirectional"))
    )
    (net (code "94") (name "Net-(U$6-XI)") (class "Default")
      (node (ref "C33") (pin "2") (pinfunction "2_2") (pintype "passive"))
      (node (ref "Q3") (pin "2") (pinfunction "2_2") (pintype "passive"))
      (node (ref "U$6") (pin "7") (pinfunction "XI_7") (pintype "bidirectional"))
    )
    (net (code "95") (name "Net-(U$6-XO)") (class "Default")
      (node (ref "C32") (pin "2") (pinfunction "2_2") (pintype "passive"))
      (node (ref "Q3") (pin "1") (pinfunction "1_1") (pintype "passive"))
      (node (ref "U$6") (pin "8") (pinfunction "XO_8") (pintype "bidirectional"))
    )
    (net (code "96") (name "VCC") (class "Default")
      (node (ref "C12") (pin "1") (pinfunction "1_1") (pintype "passive"))
      (node (ref "C17") (pin "1") (pinfunction "1_1") (pintype "passive"))
      (node (ref "C19") (pin "1") (pinfunction "1_1") (pintype "passive"))
      (node (ref "C35") (pin "2") (pinfunction "2_2") (pintype "passive"))
      (node (ref "C38") (pin "2") (pinfunction "2_2") (pintype "passive"))
      (node (ref "C43") (pin "2") (pinfunction "2_2") (pintype "passive"))
      (node (ref "C44") (pin "2") (pinfunction "2_2") (pintype "passive"))
      (node (ref "C5") (pin "1") (pinfunction "1_1") (pintype "passive"))
      (node (ref "C50") (pin "1") (pinfunction "1_1") (pintype "passive"))
      (node (ref "C51") (pin "1") (pinfunction "1_1") (pintype "passive"))
      (node (ref "C52") (pin "1") (pinfunction "1_1") (pintype "passive"))
      (node (ref "C55") (pin "+") (pinfunction "+_+") (pintype "passive"))
      (node (ref "C56") (pin "+") (pinfunction "+_+") (pintype "passive"))
      (node (ref "C57") (pin "+") (pinfunction "+_+") (pintype "passive"))
      (node (ref "C6") (pin "1") (pinfunction "1_1") (pintype "passive"))
      (node (ref "C8") (pin "1") (pinfunction "1_1") (pintype "passive"))
      (node (ref "D4") (pin "C") (pinfunction "C_C") (pintype "passive"))
      (node (ref "IC1") (pin "8") (pinfunction "V+_8") (pintype "power_in"))
      (node (ref "IC3") (pin "3") (pinfunction "IN_3") (pintype "input"))
      (node (ref "IC4") (pin "23") (pinfunction "V5_23") (pintype "bidirectional"))
      (node (ref "L1") (pin "2") (pinfunction "2_2") (pintype "passive"))
      (node (ref "PWR_HEADER") (pin "2") (pinfunction "2_2") (pintype "passive"))
      (node (ref "R13") (pin "2") (pinfunction "2_2") (pintype "passive"))
      (node (ref "R22") (pin "1") (pinfunction "1_1") (pintype "passive"))
      (node (ref "R23") (pin "2") (pinfunction "2_2") (pintype "passive"))
      (node (ref "R24") (pin "1") (pinfunction "1_1") (pintype "passive"))
      (node (ref "R9") (pin "2") (pinfunction "2_2") (pintype "passive"))
      (node (ref "RS232_SERIAL") (pin "4") (pinfunction "4_4") (pintype "passive"))
      (node (ref "TP16") (pin "TP") (pinfunction "TP_TP") (pintype "input"))
      (node (ref "TP7") (pin "TP") (pinfunction "TP_TP") (pintype "input"))
      (node (ref "U$1") (pin "29") (pinfunction "P$29_29") (pintype "bidirectional"))
      (node (ref "U$1") (pin "34") (pinfunction "P$34_34") (pintype "bidirectional"))
      (node (ref "U$1") (pin "35") (pinfunction "P$35_35") (pintype "bidirectional"))
      (node (ref "USB-P1") (pin "VBUS") (pinfunction "VBUS_VBUS") (pintype "bidirectional"))
      (node (ref "USB-P2") (pin "VBUS") (pinfunction "VBUS_VBUS") (pintype "bidirectional"))
      (node (ref "USB1") (pin "4") (pinfunction "4_4") (pintype "passive"))
      (node (ref "USB2") (pin "1") (pinfunction "1_1") (pintype "passive"))
      (node (ref "VCC_SEL") (pin "3") (pinfunction "3_3") (pintype "passive"))
    )
    (net (code "97") (name "unconnected-(IC2A-T2IN-Pad10)") (class "Default")
      (node (ref "IC2") (pin "10") (pinfunction "T2IN_10") (pintype "input"))
    )
    (net (code "98") (name "unconnected-(IC2A-T2OUT-Pad7)") (class "Default")
      (node (ref "IC2") (pin "7") (pinfunction "T2OUT_7") (pintype "output"))
    )
    (net (code "99") (name "unconnected-(IC4-OVCUR1#{slash}SMC-Pad21)") (class "Default")
      (node (ref "IC4") (pin "21") (pinfunction "OVCUR1#/SMC_21") (pintype "bidirectional"))
    )
    (net (code "100") (name "unconnected-(IC4-OVCUR2#{slash}SMD-Pad19)") (class "Default")
      (node (ref "IC4") (pin "19") (pinfunction "OVCUR2#/SMD_19") (pintype "bidirectional"))
    )
    (net (code "101") (name "unconnected-(IC4-PGANG-Pad18)") (class "Default")
      (node (ref "IC4") (pin "18") (pinfunction "PGANG_18") (pintype "bidirectional"))
    )
    (net (code "102") (name "unconnected-(IC4-PWREN1#{slash}SDA-Pad22)") (class "Default")
      (node (ref "IC4") (pin "22") (pinfunction "PWREN1#/SDA_22") (pintype "bidirectional"))
    )
    (net (code "103") (name "unconnected-(IC4-PWREN2#-Pad20)") (class "Default")
      (node (ref "IC4") (pin "20") (pinfunction "PWREN2#_20") (pintype "bidirectional"))
    )
    (net (code "104") (name "unconnected-(IC4-TEST{slash}SCL-Pad14)") (class "Default")
      (node (ref "IC4") (pin "14") (pinfunction "TEST/SCL_14") (pintype "bidirectional"))
    )
    (net (code "105") (name "unconnected-(J_PSELF1-Pad2)") (class "Default")
      (node (ref "J_PSELF1") (pin "2") (pinfunction "2_2") (pintype "passive"))
    )
    (net (code "106") (name "unconnected-(J_PSELF2-Pad2)") (class "Default")
      (node (ref "J_PSELF2") (pin "2") (pinfunction "2_2") (pintype "passive"))
    )
    (net (code "107") (name "unconnected-(SOUND-Pad7)") (class "Default")
      (node (ref "SOUND") (pin "7") (pinfunction "7_7") (pintype "passive"))
    )
    (net (code "108") (name "unconnected-(U$1-P$2-Pad2)") (class "Default")
      (node (ref "U$1") (pin "2") (pinfunction "P$2_2") (pintype "bidirectional"))
    )
    (net (code "109") (name "unconnected-(U$1-P$3-Pad3)") (class "Default")
      (node (ref "U$1") (pin "3") (pinfunction "P$3_3") (pintype "bidirectional"))
    )
    (net (code "110") (name "unconnected-(U$1-P$4-Pad4)") (class "Default")
      (node (ref "U$1") (pin "4") (pinfunction "P$4_4") (pintype "bidirectional"))
    )
    (net (code "111") (name "unconnected-(U$1-P$5-Pad5)") (class "Default")
      (node (ref "U$1") (pin "5") (pinfunction "P$5_5") (pintype "bidirectional"))
    )
    (net (code "112") (name "unconnected-(U$1-P$17-Pad17)") (class "Default")
      (node (ref "U$1") (pin "17") (pinfunction "P$17_17") (pintype "bidirectional"))
    )
    (net (code "113") (name "unconnected-(U$1-P$19-Pad19)") (class "Default")
      (node (ref "U$1") (pin "19") (pinfunction "P$19_19") (pintype "bidirectional"))
    )
    (net (code "114") (name "unconnected-(U$1-P$20-Pad20)") (class "Default")
      (node (ref "U$1") (pin "20") (pinfunction "P$20_20") (pintype "bidirectional"))
    )
    (net (code "115") (name "unconnected-(U$1-P$21-Pad21)") (class "Default")
      (node (ref "U$1") (pin "21") (pinfunction "P$21_21") (pintype "bidirectional"))
    )
    (net (code "116") (name "unconnected-(U$1-P$25-Pad25)") (class "Default")
      (node (ref "U$1") (pin "25") (pinfunction "P$25_25") (pintype "bidirectional"))
    )
    (net (code "117") (name "unconnected-(U$1-P$31-Pad31)") (class "Default")
      (node (ref "U$1") (pin "31") (pinfunction "P$31_31") (pintype "bidirectional"))
    )
    (net (code "118") (name "unconnected-(U$1-P$32-Pad32)") (class "Default")
      (node (ref "U$1") (pin "32") (pinfunction "P$32_32") (pintype "bidirectional"))
    )
    (net (code "119") (name "unconnected-(U$1-P$40-Pad40)") (class "Default")
      (node (ref "U$1") (pin "40") (pinfunction "P$40_40") (pintype "bidirectional"))
    )
    (net (code "120") (name "unconnected-(U$1-P$44-Pad44)") (class "Default")
      (node (ref "U$1") (pin "44") (pinfunction "P$44_44") (pintype "bidirectional"))
    )
    (net (code "121") (name "unconnected-(U$1-P$45-Pad45)") (class "Default")
      (node (ref "U$1") (pin "45") (pinfunction "P$45_45") (pintype "bidirectional"))
    )
    (net (code "122") (name "unconnected-(U$1-P$46-Pad46)") (class "Default")
      (node (ref "U$1") (pin "46") (pinfunction "P$46_46") (pintype "bidirectional"))
    )
    (net (code "123") (name "unconnected-(U$1-P$47-Pad47)") (class "Default")
      (node (ref "U$1") (pin "47") (pinfunction "P$47_47") (pintype "bidirectional"))
    )
    (net (code "124") (name "unconnected-(U$6-RS232-Pad15)") (class "Default")
      (node (ref "U$6") (pin "15") (pinfunction "RS232_15") (pintype "bidirectional"))
    )
    (net (code "125") (name "unconnected-(X2-Pad1)") (class "Default")
      (node (ref "X2") (pin "1") (pinfunction "1_1") (pintype "passive"))
    )
    (net (code "126") (name "unconnected-(X2-Pad4)") (class "Default")
      (node (ref "X2") (pin "4") (pinfunction "4_4") (pintype "passive"))
    )
    (net (code "127") (name "unconnected-(X2-Pad6)") (class "Default")
      (node (ref "X2") (pin "6") (pinfunction "6_6") (pintype "passive"))
    )
    (net (code "128") (name "unconnected-(X2-Pad7)") (class "Default")
      (node (ref "X2") (pin "7") (pinfunction "7_7") (pintype "passive"))
    )
    (net (code "129") (name "unconnected-(X2-Pad8)") (class "Default")
      (node (ref "X2") (pin "8") (pinfunction "8_8") (pintype "passive"))
    )
    (net (code "130") (name "unconnected-(X2-Pad9)") (class "Default")
      (node (ref "X2") (pin "9") (pinfunction "9_9") (pintype "passive"))
    )
  )
)
